# flashlightswitch01.net
KiCad netlist of a schematic drawn in EAGLE
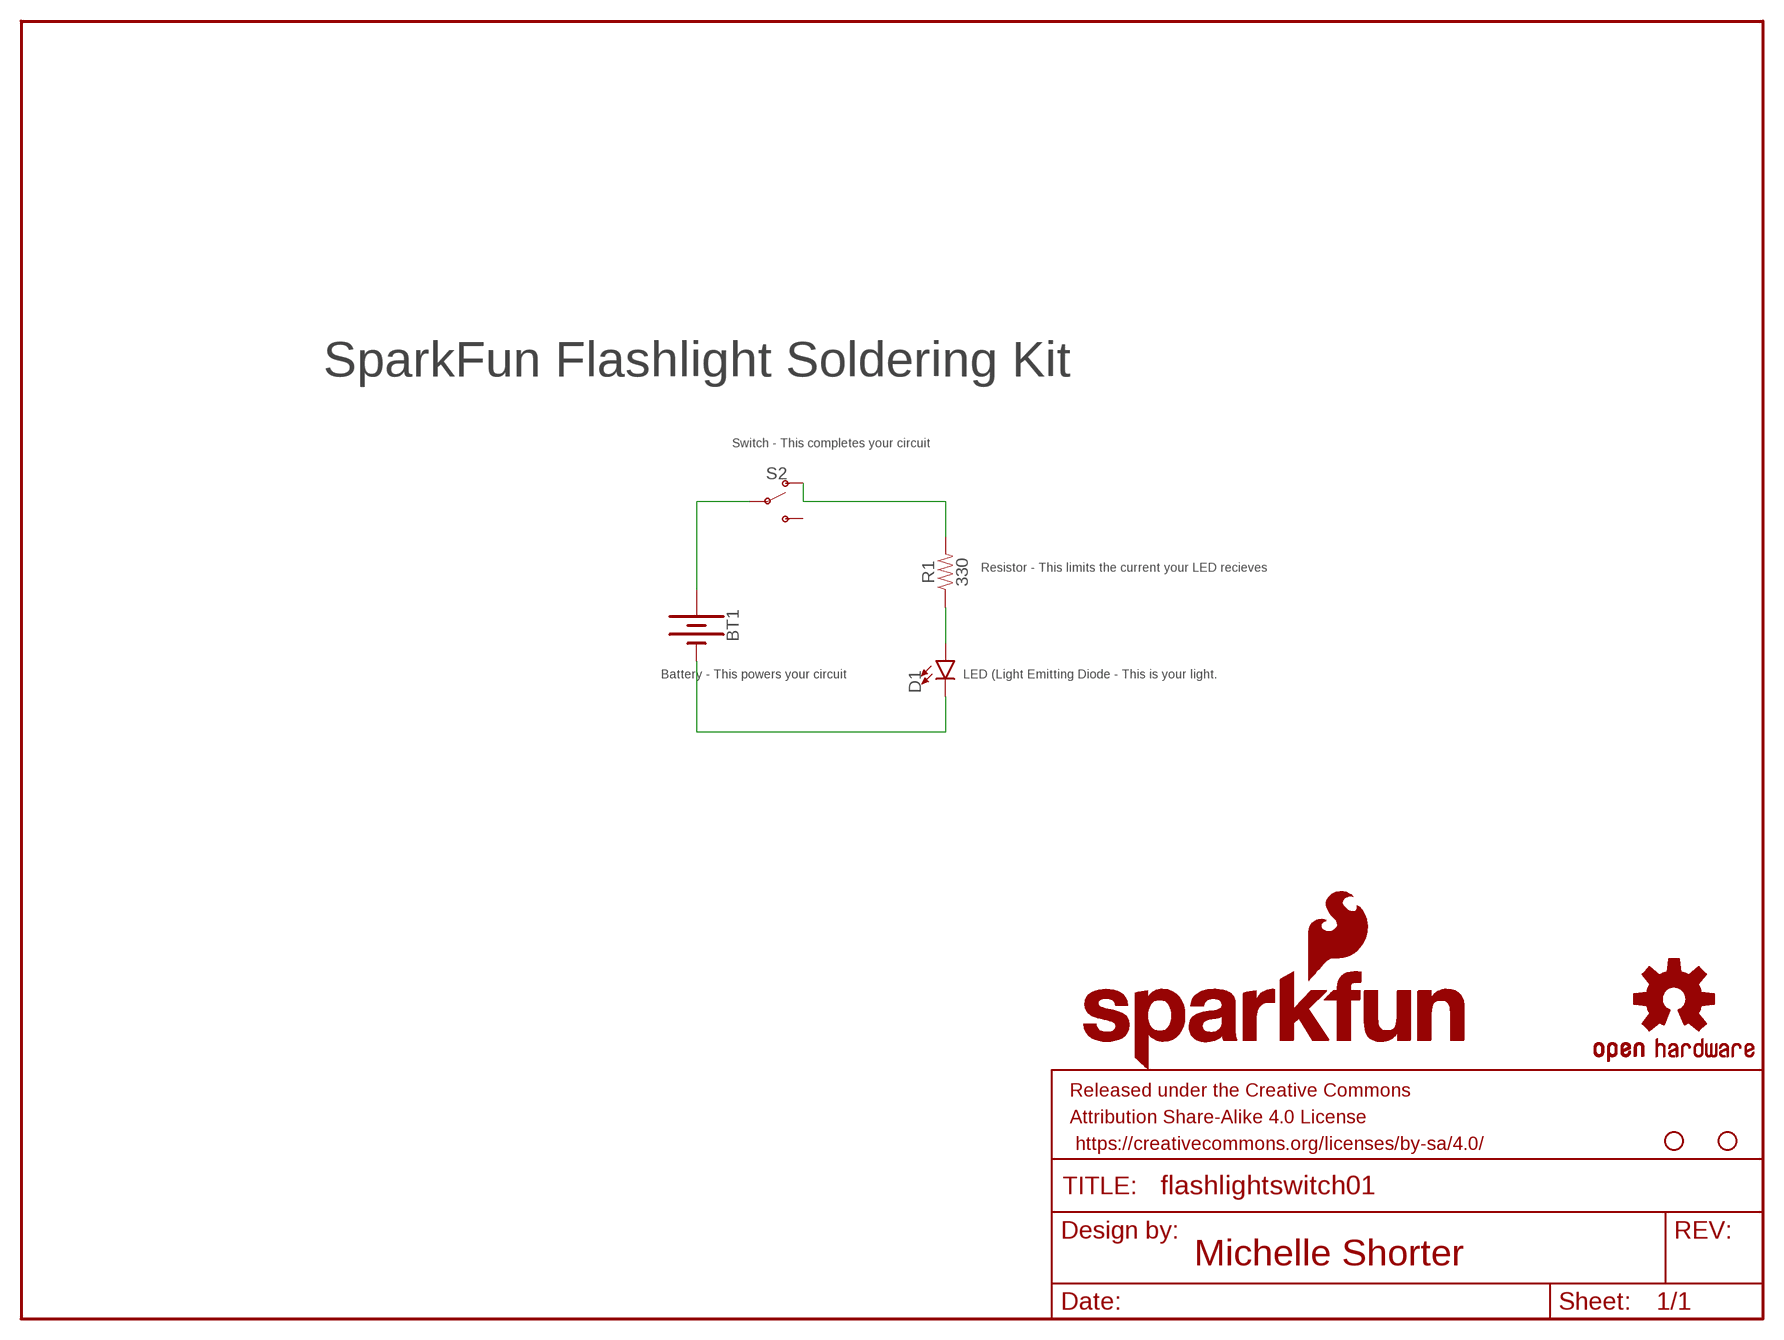
[diagram p0: schematic, sheet 1]

(export (version "E")
  (design (tool "Eeschema 10.0.6"))
  (components
    (comp (ref "BT1")
      (value "BATTERY-20MM_SMD")
      (footprint "eagle-import:BATTCON_20MM")
      (libsource (lib "eagle-import") (part "BATTERY-20MM_SMD"))
    )
    (comp (ref "D1")
      (value "LED5MM-KIT")
      (footprint "eagle-import:LED_5MM-KIT")
      (libsource (lib "eagle-import") (part "LED5MM-KIT"))
    )
    (comp (ref "FRAME1")
      (value "FRAME-LETTER")
      (footprint "eagle-import:CREATIVE_COMMONS")
      (libsource (lib "eagle-import") (part "FRAME-LETTER"))
    )
    (comp (ref "H1")
      (value "STAND-OFF")
      (footprint "eagle-import:STAND-OFF")
      (libsource (lib "eagle-import") (part "STAND-OFF"))
    )
    (comp (ref "H2")
      (value "STAND-OFF")
      (footprint "eagle-import:STAND-OFF")
      (libsource (lib "eagle-import") (part "STAND-OFF"))
    )
    (comp (ref "LOGO1")
      (value "OSHW-LOGOS")
      (footprint "eagle-import:OSHW-LOGO-S")
      (libsource (lib "eagle-import") (part "OSHW-LOGOS"))
    )
    (comp (ref "LOGO2")
      (value "SFE_LOGO_FLAME.1_INCH")
      (footprint "eagle-import:SFE_LOGO_FLAME_.1")
      (libsource (lib "eagle-import") (part "SFE_LOGO_FLAME.1_INCH"))
    )
    (comp (ref "LOGO3")
      (value "SFE_LOGO_NAME_FLAME.2_INCH")
      (footprint "eagle-import:SFE_LOGO_NAME_FLAME_.2")
      (libsource (lib "eagle-import") (part "SFE_LOGO_NAME_FLAME.2_INCH"))
    )
    (comp (ref "LOGO4")
      (value "SFE_LOGO_NAME.1_INCH")
      (footprint "eagle-import:SFE_LOGO_NAME_.1")
      (libsource (lib "eagle-import") (part "SFE_LOGO_NAME.1_INCH"))
    )
    (comp (ref "R1")
      (value "330")
      (footprint "eagle-import:AXIAL-0.3-KIT")
      (libsource (lib "eagle-import") (part "RESISTORAXIAL-0.3-KIT"))
    )
    (comp (ref "S2")
      (value "SWITCH-SPDT-PTH-11.6X4.0MM-KIT")
      (footprint "eagle-import:SWITCH_SPDT_PTH_11.6X4.0MM_KIT")
      (libsource (lib "eagle-import") (part "SWITCH-SPDT-PTH-11.6X4.0MM-KIT"))
    )
  )
  (nets
    (net (code "1") (name "Net-(BT1-+)") (class "Default")
      (node (ref "BT1") (pin "1") (pinfunction "+_1") (pintype "power_in"))
      (node (ref "S2") (pin "2") (pinfunction "P_2") (pintype "passive"))
    )
    (net (code "2") (name "Net-(BT1--)") (class "Default")
      (node (ref "BT1") (pin "2") (pinfunction "-_2") (pintype "power_in"))
      (node (ref "D1") (pin "K") (pinfunction "C_K") (pintype "passive"))
    )
    (net (code "3") (name "Net-(R1-1)") (class "Default")
      (node (ref "D1") (pin "A") (pinfunction "A_A") (pintype "passive"))
      (node (ref "R1") (pin "P$1") (pinfunction "1_P$1") (pintype "passive"))
    )
    (net (code "4") (name "Net-(R1-2)") (class "Default")
      (node (ref "R1") (pin "P$2") (pinfunction "2_P$2") (pintype "passive"))
      (node (ref "S2") (pin "1") (pinfunction "O_1") (pintype "passive"))
    )
    (net (code "5") (name "unconnected-(S2-S-Pad3)") (class "Default")
      (node (ref "S2") (pin "3") (pinfunction "S_3") (pintype "passive"))
    )
  )
)
